# 2_Power.net
KiCad netlist of a schematic drawn in Altium Designer
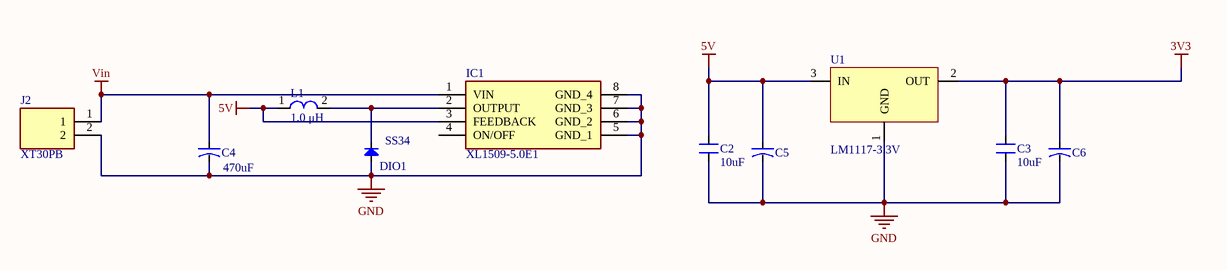
[diagram p0: [2]Power.SchDoc]

(export (version "E")
  (design (tool "Eeschema 10.0.6"))
  (components
    (comp (ref "C2")
      (value "10uF")
      (footprint "CN-SMD-0603")
      (description "Tu gom")
      (libsource (lib "LIBTanCN") (part "CN"))
    )
    (comp (ref "C3")
      (value "10uF")
      (footprint "CN-SMD-0603")
      (description "Tu gom")
      (libsource (lib "LIBTanCN") (part "CN"))
    )
    (comp (ref "C4")
      (value "470uF")
      (footprint "CAP-ALU-SMD-6.3x7.7x2.2")
      (description "Polarized Capacitor (Axial)")
      (fields (field (name "PUBLISHER") "Altium Limited"))
      (libsource (lib "LIBTanCN") (part "CN-ALU-SMD"))
    )
    (comp (ref "C5")
      (value "CN-ALU-SMD")
      (footprint "CAP-ALU-SMD-4.5x5x1.4")
      (description "Polarized Capacitor (Axial)")
      (fields (field (name "PUBLISHER") "Altium Limited"))
      (libsource (lib "LIBTanCN") (part "CN-ALU-SMD"))
    )
    (comp (ref "C6")
      (value "CN-ALU-SMD")
      (footprint "CAP-ALU-SMD-4.5x5x1.4")
      (description "Polarized Capacitor (Axial)")
      (fields (field (name "PUBLISHER") "Altium Limited"))
      (libsource (lib "LIBTanCN") (part "CN-ALU-SMD"))
    )
    (comp (ref "DIO1")
      (value "SS34")
      (footprint "DIO-SMD-106")
      (description "Default Diode")
      (fields (field (name "PUBLISHER") "Altium Limited"))
      (libsource (lib "LIBRARY") (part "Diode SMD"))
    )
    (comp (ref "IC1")
      (value "XL1509-5.0E1")
      (footprint "SamacSys:SOIC127P600X175-8N")
      (description "Integrated Circuit")
      (libsource (lib "SamacSys") (part "XL1509-5.0E1"))
    )
    (comp (ref "J2")
      (value "XT30PB")
      (footprint "SamacSys:XT30PB")
      (description "Connector")
      (libsource (lib "*") (part "XT30PB"))
    )
    (comp (ref "L1")
      (value "1.0 μH")
      (footprint "L-SMD-M-7.3x4.5")
      (fields
        (field (name "PARTNO") "78477010")
        (field (name "MANUFACTURER") "Wurth Elektronik")
        (field (name "CREATED BY") "Baojun Chen")
      )
      (libsource (lib "LIBTanCN") (part "L-SMD-1"))
    )
    (comp (ref "U1")
      (value "LM1117-3.3V")
      (footprint "SOT223")
      (description "800mA Low-Dropout Linear Regulator")
      (fields (field (name "CREATOR") "Nguyen Ba Bien"))
      (libsource (lib "LIBRARY") (part "LM1117"))
    )
  )
  (nets
    (net (code "1") (name "3V3") (class "Default")
      (node (ref "C3") (pin "1") (pinfunction "1_1") (pintype "passive"))
      (node (ref "C6") (pin "1") (pinfunction "1_1") (pintype "passive"))
      (node (ref "U1") (pin "2") (pinfunction "OUT_2") (pintype "passive"))
    )
    (net (code "2") (name "5V") (class "Default")
      (node (ref "C2") (pin "1") (pinfunction "1_1") (pintype "passive"))
      (node (ref "C5") (pin "1") (pinfunction "1_1") (pintype "passive"))
      (node (ref "IC1") (pin "3") (pinfunction "FEEDBACK_3") (pintype "passive"))
      (node (ref "L1") (pin "1") (pinfunction "1_1") (pintype "passive"))
      (node (ref "U1") (pin "3") (pinfunction "IN_3") (pintype "passive"))
    )
    (net (code "3") (name "GND") (class "Default")
      (node (ref "C2") (pin "2") (pinfunction "2_2") (pintype "passive"))
      (node (ref "C3") (pin "2") (pinfunction "2_2") (pintype "passive"))
      (node (ref "C4") (pin "2") (pinfunction "2_2") (pintype "passive"))
      (node (ref "C5") (pin "2") (pinfunction "2_2") (pintype "passive"))
      (node (ref "C6") (pin "2") (pinfunction "2_2") (pintype "passive"))
      (node (ref "DIO1") (pin "1") (pinfunction "A_1") (pintype "passive"))
      (node (ref "IC1") (pin "5") (pinfunction "GND_1_5") (pintype "passive"))
      (node (ref "IC1") (pin "6") (pinfunction "GND_2_6") (pintype "passive"))
      (node (ref "IC1") (pin "7") (pinfunction "GND_3_7") (pintype "passive"))
      (node (ref "IC1") (pin "8") (pinfunction "GND_4_8") (pintype "passive"))
      (node (ref "J2") (pin "2") (pinfunction "2_2") (pintype "passive"))
      (node (ref "U1") (pin "1") (pinfunction "GND_1") (pintype "passive"))
    )
    (net (code "4") (name "Net-(DIO1-K)") (class "Default")
      (node (ref "DIO1") (pin "2") (pinfunction "K_2") (pintype "passive"))
      (node (ref "IC1") (pin "2") (pinfunction "OUTPUT_2") (pintype "passive"))
      (node (ref "L1") (pin "2") (pinfunction "2_2") (pintype "passive"))
    )
    (net (code "5") (name "Vin") (class "Default")
      (node (ref "C4") (pin "1") (pinfunction "1_1") (pintype "passive"))
      (node (ref "IC1") (pin "1") (pinfunction "VIN_1") (pintype "passive"))
      (node (ref "J2") (pin "1") (pinfunction "1_1") (pintype "passive"))
    )
    (net (code "6") (name "unconnected-(IC1-ON{slash}OFF-Pad4)") (class "Default")
      (node (ref "IC1") (pin "4") (pinfunction "ON/OFF_4") (pintype "passive"))
    )
  )
)
